# CMP3_Amp.net
KiCad netlist of a schematic drawn in EAGLE
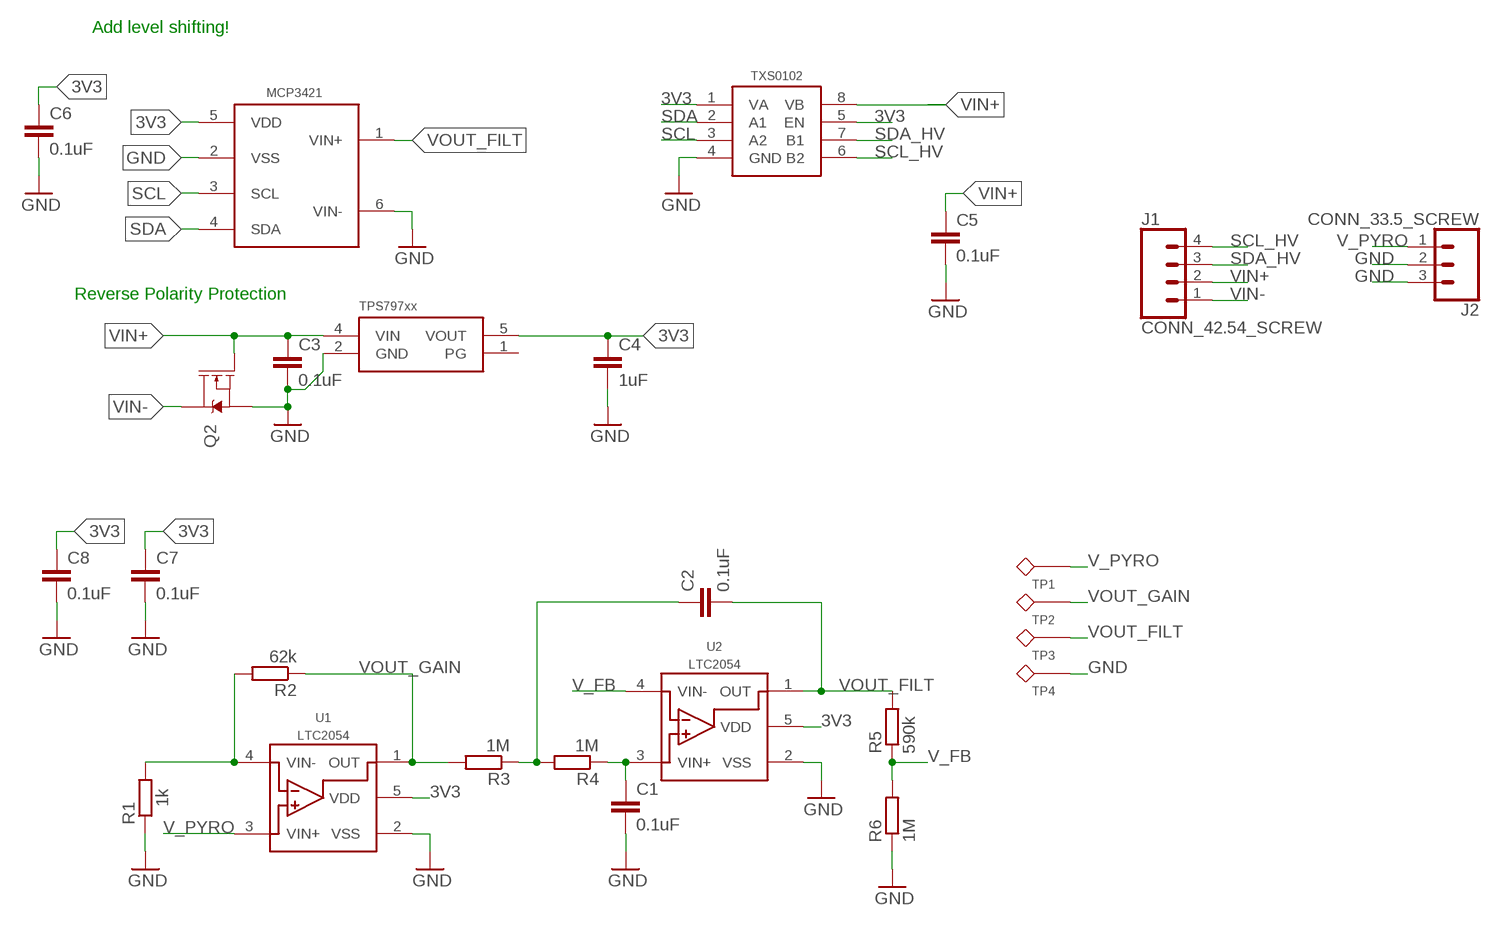
[diagram p0: schematic, sheet 1]

(export (version "E")
  (design (tool "Eeschema 10.0.6"))
  (components
    (comp (ref "C1")
      (value "0.1uF")
      (footprint "eagle-import:C0603")
      (fields (field (name "MF") "Murata") (field (name "MPN") "GCM188R71E104KA57D"))
      (libsource (lib "eagle-import") (part "C-EUC06030.1UF"))
    )
    (comp (ref "C2")
      (value "0.1uF")
      (footprint "eagle-import:C0603")
      (fields (field (name "MF") "Murata") (field (name "MPN") "GCM188R71E104KA57D"))
      (libsource (lib "eagle-import") (part "C-EUC06030.1UF"))
    )
    (comp (ref "C3")
      (value "0.1uF")
      (footprint "eagle-import:C0603")
      (fields (field (name "MF") "Murata") (field (name "MPN") "GCM188R71E104KA57D"))
      (libsource (lib "eagle-import") (part "C-EUC06030.1UF"))
    )
    (comp (ref "C4")
      (value "1uF")
      (footprint "eagle-import:C0603")
      (fields (field (name "MF") "Murata") (field (name "MPN") "GRM188R61C105KA12D"))
      (libsource (lib "eagle-import") (part "C-EUC06031UF"))
    )
    (comp (ref "C5")
      (value "0.1uF")
      (footprint "eagle-import:C0402")
      (fields (field (name "MF") "Murata") (field (name "MPN") "GCM155R71C104KA55D"))
      (libsource (lib "eagle-import") (part "C-EUC04020.1UF"))
    )
    (comp (ref "C6")
      (value "0.1uF")
      (footprint "eagle-import:C0402")
      (fields (field (name "MF") "Murata") (field (name "MPN") "GCM155R71C104KA55D"))
      (libsource (lib "eagle-import") (part "C-EUC04020.1UF"))
    )
    (comp (ref "C7")
      (value "0.1uF")
      (footprint "eagle-import:C0402")
      (fields (field (name "MF") "Murata") (field (name "MPN") "GCM155R71C104KA55D"))
      (libsource (lib "eagle-import") (part "C-EUC04020.1UF"))
    )
    (comp (ref "C8")
      (value "0.1uF")
      (footprint "eagle-import:C0402")
      (fields (field (name "MF") "Murata") (field (name "MPN") "GCM155R71C104KA55D"))
      (libsource (lib "eagle-import") (part "C-EUC04020.1UF"))
    )
    (comp (ref "J1")
      (value "CONN_42.54_SCREW")
      (footprint "eagle-import:1X04_SCREW")
      (fields (field (name "MF") "On Shore") (field (name "MPN") "OSTVN04A150"))
      (libsource (lib "eagle-import") (part "CONN_42.54_SCREW"))
    )
    (comp (ref "J2")
      (value "CONN_33.5_SCREW")
      (footprint "eagle-import:1X03_3.5MM_SCREW")
      (fields (field (name "MF") "OnShore") (field (name "MPN") "OSTTE030161"))
      (libsource (lib "eagle-import") (part "CONN_33.5_SCREW"))
    )
    (comp (ref "Q2")
      (value "DMG3404")
      (footprint "eagle-import:SOT23-3")
      (fields (field (name "MF") "Diodes Incorporated") (field (name "MPN") "DMG3404L-7"))
      (libsource (lib "eagle-import") (part "MOSFET-NCH-DMG3404L"))
    )
    (comp (ref "R1")
      (value "1k")
      (footprint "eagle-import:R0603")
      (fields (field (name "MF") "Panasonic") (field (name "MPN") "ERA-3AEB102V"))
      (libsource (lib "eagle-import") (part "R-EU_R0603P1K"))
    )
    (comp (ref "R2")
      (value "62k")
      (footprint "eagle-import:R0603")
      (fields (field (name "MF") "Panasonic") (field (name "MPN") "ERA-3AEB623V"))
      (libsource (lib "eagle-import") (part "R-EU_R0603P62K"))
    )
    (comp (ref "R3")
      (value "1M")
      (footprint "eagle-import:R0603")
      (fields (field (name "MF") "Panasonic") (field (name "MPN") "ERJ-3EKF1004V"))
      (libsource (lib "eagle-import") (part "R-EU_R06031M"))
    )
    (comp (ref "R4")
      (value "1M")
      (footprint "eagle-import:R0603")
      (fields (field (name "MF") "Panasonic") (field (name "MPN") "ERJ-3EKF1004V"))
      (libsource (lib "eagle-import") (part "R-EU_R06031M"))
    )
    (comp (ref "R5")
      (value "590k")
      (footprint "eagle-import:R0603")
      (fields (field (name "MF") "Yageo") (field (name "MPN") "RC0603FR-07590KL"))
      (libsource (lib "eagle-import") (part "R-EU_R0603590K"))
    )
    (comp (ref "R6")
      (value "1M")
      (footprint "eagle-import:R0603")
      (fields (field (name "MF") "Panasonic") (field (name "MPN") "ERJ-3EKF1004V"))
      (libsource (lib "eagle-import") (part "R-EU_R06031M"))
    )
    (comp (ref "TP1")
      (value "TESTPOINTRCU")
      (footprint "eagle-import:TESTPOINT_0603")
      (fields (field (name "MF") "TE Connectivity") (field (name "MPN") "RCU-0C"))
      (libsource (lib "eagle-import") (part "TESTPOINTRCU"))
    )
    (comp (ref "TP2")
      (value "TESTPOINTRCU")
      (footprint "eagle-import:TESTPOINT_0603")
      (fields (field (name "MF") "TE Connectivity") (field (name "MPN") "RCU-0C"))
      (libsource (lib "eagle-import") (part "TESTPOINTRCU"))
    )
    (comp (ref "TP3")
      (value "TESTPOINTRCU")
      (footprint "eagle-import:TESTPOINT_0603")
      (fields (field (name "MF") "TE Connectivity") (field (name "MPN") "RCU-0C"))
      (libsource (lib "eagle-import") (part "TESTPOINTRCU"))
    )
    (comp (ref "TP4")
      (value "TESTPOINTRCU")
      (footprint "eagle-import:TESTPOINT_0603")
      (fields (field (name "MF") "TE Connectivity") (field (name "MPN") "RCU-0C"))
      (libsource (lib "eagle-import") (part "TESTPOINTRCU"))
    )
    (comp (ref "U1")
      (value "LTC2054")
      (footprint "eagle-import:SOT23-5")
      (fields
        (field (name "DISP") "LTC2054")
        (field (name "MF") "LT")
        (field (name "MPN") "LTC2054HS5#TRMPBF")
      )
      (libsource (lib "eagle-import") (part "LTC2054"))
    )
    (comp (ref "U2")
      (value "LTC2054")
      (footprint "eagle-import:SOT23-5")
      (fields
        (field (name "DISP") "LTC2054")
        (field (name "MF") "LT")
        (field (name "MPN") "LTC2054HS5#TRMPBF")
      )
      (libsource (lib "eagle-import") (part "LTC2054"))
    )
    (comp (ref "U3")
      (value "MCP3421A1")
      (footprint "eagle-import:SOT23-6L")
      (fields
        (field (name "DISP") "MCP3421")
        (field (name "MF") "Microchip")
        (field (name "MPN") "MCP3421A1T-E/CH")
      )
      (libsource (lib "eagle-import") (part "MCP3421A1"))
    )
    (comp (ref "U4")
      (value "TXS0102DQM")
      (footprint "eagle-import:DQM_R-PX2SON-N8")
      (fields (field (name "MF") "TI") (field (name "MPN") "TXS0102DQMR"))
      (libsource (lib "eagle-import") (part "TXS0102DQM"))
    )
    (comp (ref "U5")
      (value "TPS79733")
      (footprint "eagle-import:DCK_R-PDSO-G5")
      (fields (field (name "MF") "TI") (field (name "MPN") "TPS79733DCKR"))
      (libsource (lib "eagle-import") (part "TPS79733"))
    )
  )
  (nets
    (net (code "1") (name "/SCL_HV") (class "Default")
      (node (ref "J1") (pin "4") (pinfunction "4_4") (pintype "passive"))
      (node (ref "U4") (pin "6") (pinfunction "B2_6") (pintype "bidirectional"))
    )
    (net (code "2") (name "/SDA_HV") (class "Default")
      (node (ref "J1") (pin "3") (pinfunction "3_3") (pintype "passive"))
      (node (ref "U4") (pin "7") (pinfunction "B1_7") (pintype "bidirectional"))
    )
    (net (code "3") (name "/VOUT_GAIN") (class "Default")
      (node (ref "R2") (pin "1") (pinfunction "1_1") (pintype "passive"))
      (node (ref "R3") (pin "2") (pinfunction "2_2") (pintype "passive"))
      (node (ref "TP2") (pin "1") (pinfunction "P$1_1") (pintype "bidirectional"))
      (node (ref "U1") (pin "1") (pinfunction "OUT_1") (pintype "output"))
    )
    (net (code "4") (name "/V_FB") (class "Default")
      (node (ref "R5") (pin "1") (pinfunction "1_1") (pintype "passive"))
      (node (ref "R6") (pin "2") (pinfunction "2_2") (pintype "passive"))
      (node (ref "U2") (pin "4") (pinfunction "VIN-_4") (pintype "input"))
    )
    (net (code "5") (name "/V_PYRO") (class "Default")
      (node (ref "J2") (pin "1") (pinfunction "1_1") (pintype "passive"))
      (node (ref "TP1") (pin "1") (pinfunction "P$1_1") (pintype "bidirectional"))
      (node (ref "U1") (pin "3") (pinfunction "VIN+_3") (pintype "input"))
    )
    (net (code "6") (name "3V3") (class "Default")
      (node (ref "C4") (pin "1") (pinfunction "1_1") (pintype "passive"))
      (node (ref "C6") (pin "1") (pinfunction "1_1") (pintype "passive"))
      (node (ref "C7") (pin "1") (pinfunction "1_1") (pintype "passive"))
      (node (ref "C8") (pin "1") (pinfunction "1_1") (pintype "passive"))
      (node (ref "U1") (pin "5") (pinfunction "VDD_5") (pintype "power_in"))
      (node (ref "U2") (pin "5") (pinfunction "VDD_5") (pintype "power_in"))
      (node (ref "U3") (pin "5") (pinfunction "VDD_5") (pintype "passive"))
      (node (ref "U4") (pin "1") (pinfunction "VA_1") (pintype "power_in"))
      (node (ref "U4") (pin "5") (pinfunction "EN_5") (pintype "input"))
      (node (ref "U5") (pin "5") (pinfunction "VOUT_5") (pintype "bidirectional"))
    )
    (net (code "7") (name "GND") (class "Default")
      (node (ref "C1") (pin "2") (pinfunction "2_2") (pintype "passive"))
      (node (ref "C3") (pin "2") (pinfunction "2_2") (pintype "passive"))
      (node (ref "C4") (pin "2") (pinfunction "2_2") (pintype "passive"))
      (node (ref "C5") (pin "2") (pinfunction "2_2") (pintype "passive"))
      (node (ref "C6") (pin "2") (pinfunction "2_2") (pintype "passive"))
      (node (ref "C7") (pin "2") (pinfunction "2_2") (pintype "passive"))
      (node (ref "C8") (pin "2") (pinfunction "2_2") (pintype "passive"))
      (node (ref "J2") (pin "2") (pinfunction "2_2") (pintype "passive"))
      (node (ref "J2") (pin "3") (pinfunction "3_3") (pintype "passive"))
      (node (ref "Q2") (pin "2") (pinfunction "S_2") (pintype "bidirectional"))
      (node (ref "R1") (pin "1") (pinfunction "1_1") (pintype "passive"))
      (node (ref "R6") (pin "1") (pinfunction "1_1") (pintype "passive"))
      (node (ref "TP4") (pin "1") (pinfunction "P$1_1") (pintype "bidirectional"))
      (node (ref "U1") (pin "2") (pinfunction "VSS_2") (pintype "power_in"))
      (node (ref "U2") (pin "2") (pinfunction "VSS_2") (pintype "power_in"))
      (node (ref "U3") (pin "2") (pinfunction "VSS_2") (pintype "passive"))
      (node (ref "U3") (pin "6") (pinfunction "VIN-_6") (pintype "input"))
      (node (ref "U4") (pin "4") (pinfunction "GND_4") (pintype "power_in"))
      (node (ref "U5") (pin "2") (pinfunction "GND_2") (pintype "bidirectional"))
    )
    (net (code "8") (name "Net-(C2-Pad1)") (class "Default")
      (node (ref "C2") (pin "1") (pinfunction "1_1") (pintype "passive"))
      (node (ref "R3") (pin "1") (pinfunction "1_1") (pintype "passive"))
      (node (ref "R4") (pin "2") (pinfunction "2_2") (pintype "passive"))
    )
    (net (code "9") (name "Net-(U1-VIN-)") (class "Default")
      (node (ref "R1") (pin "2") (pinfunction "2_2") (pintype "passive"))
      (node (ref "R2") (pin "2") (pinfunction "2_2") (pintype "passive"))
      (node (ref "U1") (pin "4") (pinfunction "VIN-_4") (pintype "input"))
    )
    (net (code "10") (name "Net-(U2-VIN+)") (class "Default")
      (node (ref "C1") (pin "1") (pinfunction "1_1") (pintype "passive"))
      (node (ref "R4") (pin "1") (pinfunction "1_1") (pintype "passive"))
      (node (ref "U2") (pin "3") (pinfunction "VIN+_3") (pintype "input"))
    )
    (net (code "11") (name "SCL") (class "Default")
      (node (ref "U3") (pin "3") (pinfunction "SCL_3") (pintype "bidirectional"))
      (node (ref "U4") (pin "3") (pinfunction "A2_3") (pintype "bidirectional"))
    )
    (net (code "12") (name "SDA") (class "Default")
      (node (ref "U3") (pin "4") (pinfunction "SDA_4") (pintype "bidirectional"))
      (node (ref "U4") (pin "2") (pinfunction "A1_2") (pintype "bidirectional"))
    )
    (net (code "13") (name "VIN+") (class "Default")
      (node (ref "C3") (pin "1") (pinfunction "1_1") (pintype "passive"))
      (node (ref "C5") (pin "1") (pinfunction "1_1") (pintype "passive"))
      (node (ref "J1") (pin "2") (pinfunction "2_2") (pintype "passive"))
      (node (ref "Q2") (pin "1") (pinfunction "G_1") (pintype "bidirectional"))
      (node (ref "U4") (pin "8") (pinfunction "VB_8") (pintype "power_in"))
      (node (ref "U5") (pin "4") (pinfunction "VIN_4") (pintype "bidirectional"))
    )
    (net (code "14") (name "VIN-") (class "Default")
      (node (ref "J1") (pin "1") (pinfunction "1_1") (pintype "passive"))
      (node (ref "Q2") (pin "3") (pinfunction "D_3") (pintype "bidirectional"))
    )
    (net (code "15") (name "VOUT_FILT") (class "Default")
      (node (ref "C2") (pin "2") (pinfunction "2_2") (pintype "passive"))
      (node (ref "R5") (pin "2") (pinfunction "2_2") (pintype "passive"))
      (node (ref "TP3") (pin "1") (pinfunction "P$1_1") (pintype "bidirectional"))
      (node (ref "U2") (pin "1") (pinfunction "OUT_1") (pintype "output"))
      (node (ref "U3") (pin "1") (pinfunction "VIN+_1") (pintype "input"))
    )
    (net (code "16") (name "unconnected-(U5-PG-Pad1)") (class "Default")
      (node (ref "U5") (pin "1") (pinfunction "PG_1") (pintype "bidirectional"))
    )
  )
)
